# Sinaliza_o_Leds_Buzzer_Conversor_N_vel_L.net
KiCad netlist of a schematic drawn in Altium Designer
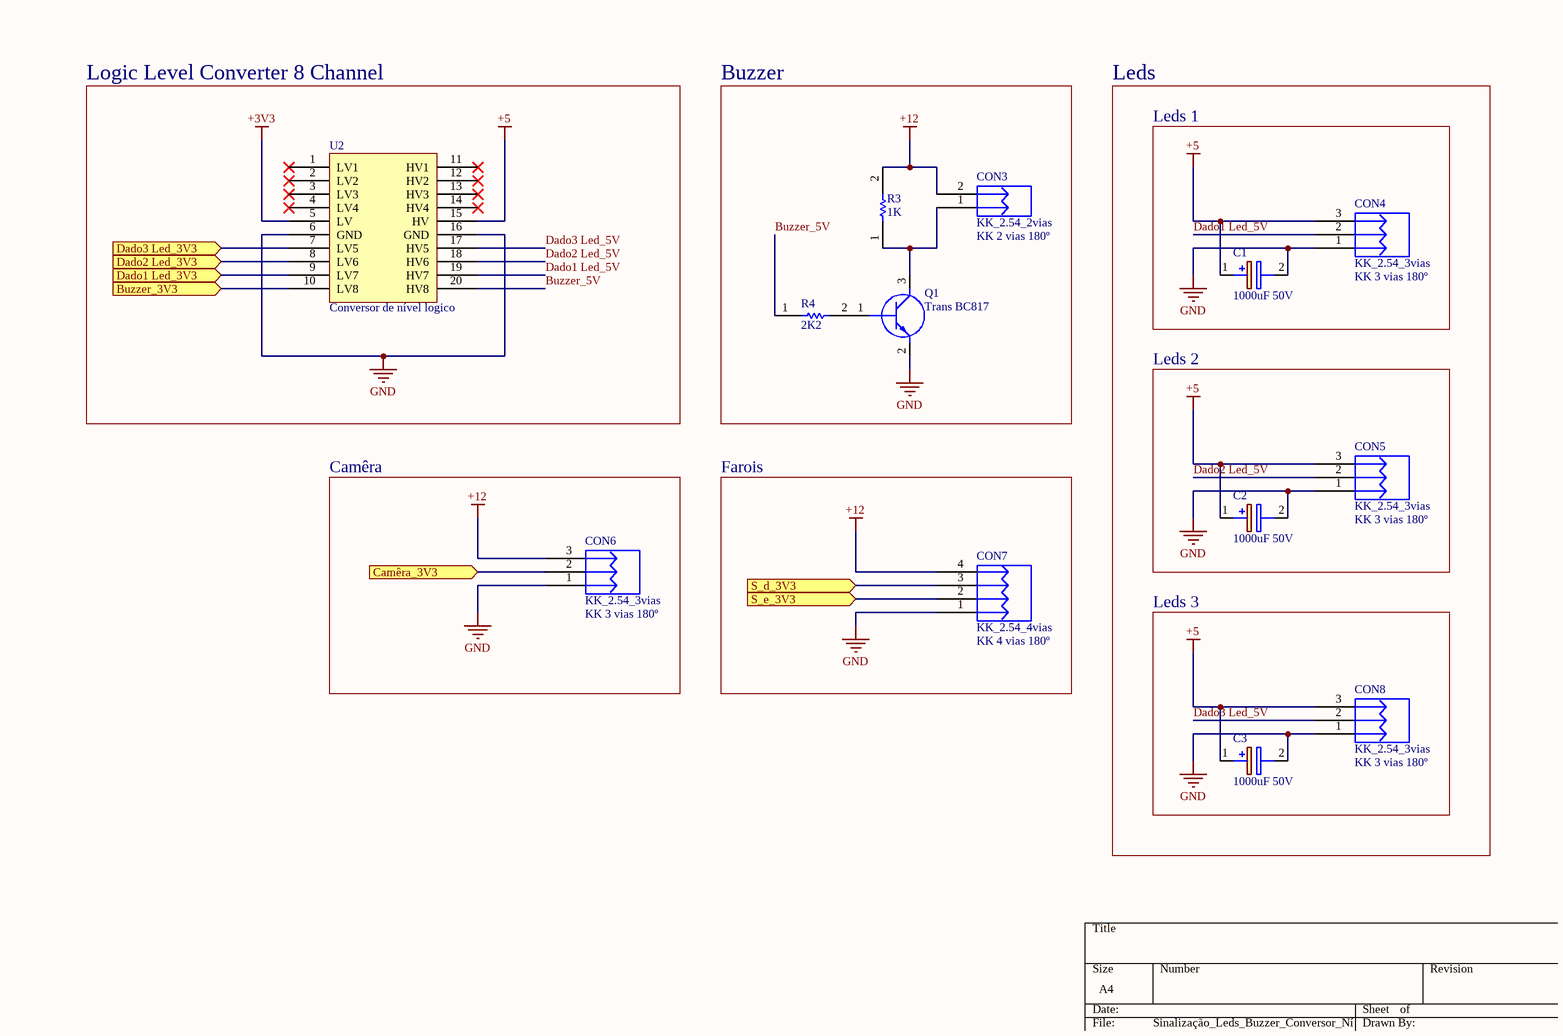
[diagram p0: Sinalização_Leds_Buzzer_Conversor_Nível_Lógico.SchDoc]

(export (version "E")
  (design (tool "Eeschema 10.0.6"))
  (components
    (comp (ref "C1")
      (value "1000uF 50V")
      (footprint "SamacSys:CAPPRD500W62D1300H2650")
      (description "Capacitor Eletrolitico 1000uF 50V")
      (fields
        (field (name "MANUFACTURER_PART_NUMBER") "860010678024")
        (field (name "MOUSER PART NUMBER") "710-860010678024")
      )
      (libsource (lib "Sinalização_Official") (part "1000uF 50V"))
    )
    (comp (ref "C2")
      (value "1000uF 50V")
      (footprint "SamacSys:CAPPRD500W62D1300H2650")
      (description "Capacitor Eletrolitico 1000uF 50V")
      (fields
        (field (name "MANUFACTURER_PART_NUMBER") "860010678024")
        (field (name "MOUSER PART NUMBER") "710-860010678024")
      )
      (libsource (lib "Sinalização_Official") (part "1000uF 50V"))
    )
    (comp (ref "C3")
      (value "1000uF 50V")
      (footprint "SamacSys:CAPPRD500W62D1300H2650")
      (description "Capacitor Eletrolitico 1000uF 50V")
      (fields
        (field (name "MANUFACTURER_PART_NUMBER") "860010678024")
        (field (name "MOUSER PART NUMBER") "710-860010678024")
      )
      (libsource (lib "Sinalização_Official") (part "1000uF 50V"))
    )
    (comp (ref "CON3")
      (value "KK_2.54_2vias")
      (footprint "KK_2VIAS_180º")
      (description "Conector KK 2.54mm 2 vias")
      (fields (field (name "VALOR") "KK 2 vias 180º"))
      (libsource (lib "Sinalização_Official") (part "KK_2.54_2vias"))
    )
    (comp (ref "CON4")
      (value "KK_2.54_3vias")
      (footprint "KK_3vias_180º")
      (description "Conector KK 2.54mm 3 vias")
      (fields (field (name "VALOR") "KK 3 vias 180º"))
      (libsource (lib "Sinalização_Official") (part "KK_2.54_3vias"))
    )
    (comp (ref "CON5")
      (value "KK_2.54_3vias")
      (footprint "KK_3vias_180º")
      (description "Conector KK 2.54mm 3 vias")
      (fields (field (name "VALOR") "KK 3 vias 180º"))
      (libsource (lib "Sinalização_Official") (part "KK_2.54_3vias"))
    )
    (comp (ref "CON6")
      (value "KK_2.54_3vias")
      (footprint "KK_3vias_180º")
      (description "Conector KK 2.54mm 3 vias")
      (fields (field (name "VALOR") "KK 3 vias 180º"))
      (libsource (lib "Sinalização_Official") (part "KK_2.54_3vias"))
    )
    (comp (ref "CON7")
      (value "KK_2.54_4vias")
      (footprint "KK_4vias_180°")
      (description "Conector KK 2.54mm 4 vias")
      (fields (field (name "VALOR") "KK 4 vias 180º"))
      (libsource (lib "Sinalização_Official") (part "KK_2.54_4vias"))
    )
    (comp (ref "CON8")
      (value "KK_2.54_3vias")
      (footprint "KK_3vias_180º")
      (description "Conector KK 2.54mm 3 vias")
      (fields (field (name "VALOR") "KK 3 vias 180º"))
      (libsource (lib "Sinalização_Official") (part "KK_2.54_3vias"))
    )
    (comp (ref "Q1")
      (value "Trans BC817")
      (footprint "SamacSys:SOT96P240X110-3N")
      (description "Transistor BJT NPN BC817-25-7-F")
      (fields
        (field (name "MANUFACTURER_PART_NUMBER") "BC817-25-7-F")
        (field (name "MOUSER PART NUMBER") "621-BC817-25-7-F")
      )
      (libsource (lib "Sinalização_Official") (part "Trans BC817"))
    )
    (comp (ref "R3")
      (value "1K")
      (footprint "SamacSys:RESC3216X60N")
      (description "Resistor")
      (fields
        (field (name "MANUFACTURER_PART_NUMBER") "CRCW12064K70FKEA")
        (field (name "MOUSER PART NUMBER") "71-CRCW1206-4.7K-E3")
      )
      (libsource (lib "Sinalização_Official") (part "Resistor 1206"))
    )
    (comp (ref "R4")
      (value "2K2")
      (footprint "SamacSys:RESC3216X60N")
      (description "Resistor")
      (fields
        (field (name "MANUFACTURER_PART_NUMBER") "CRCW12064K70FKEA")
        (field (name "MOUSER PART NUMBER") "71-CRCW1206-4.7K-E3")
      )
      (libsource (lib "Sinalização_Official") (part "Resistor 1206"))
    )
    (comp (ref "U2")
      (value "Conversor de nível logico")
      (footprint "Conversor de nível lógico")
      (libsource (lib "Sinalização_Official") (part "Conversor de nível logico"))
    )
  )
  (nets
    (net (code "1") (name "+3V3") (class "Default")
      (node (ref "U2") (pin "5") (pinfunction "LV_5") (pintype "passive"))
    )
    (net (code "2") (name "+5") (class "Default")
      (node (ref "C1") (pin "1") (pinfunction "+_1") (pintype "passive"))
      (node (ref "C2") (pin "1") (pinfunction "+_1") (pintype "passive"))
      (node (ref "C3") (pin "1") (pinfunction "+_1") (pintype "passive"))
      (node (ref "CON4") (pin "3") (pintype "passive"))
      (node (ref "CON5") (pin "3") (pintype "passive"))
      (node (ref "CON8") (pin "3") (pintype "passive"))
      (node (ref "U2") (pin "15") (pinfunction "HV_15") (pintype "passive"))
    )
    (net (code "3") (name "+12") (class "Default")
      (node (ref "CON3") (pin "2") (pintype "passive"))
      (node (ref "CON6") (pin "3") (pintype "passive"))
      (node (ref "CON7") (pin "4") (pintype "passive"))
      (node (ref "R3") (pin "2") (pinfunction "2_2") (pintype "passive"))
    )
    (net (code "4") (name "/Buzzer_3V3") (class "Default")
      (node (ref "U2") (pin "10") (pinfunction "LV8_10") (pintype "passive"))
    )
    (net (code "5") (name "/Buzzer_5V") (class "Default")
      (node (ref "R4") (pin "1") (pinfunction "1_1") (pintype "passive"))
      (node (ref "U2") (pin "20") (pinfunction "HV8_20") (pintype "passive"))
    )
    (net (code "6") (name "/Camêra_3V3") (class "Default") (node (ref "CON6") (pin "2") (pintype "passive")))
    (net (code "7") (name "/Dado1 Led_3V3") (class "Default")
      (node (ref "U2") (pin "9") (pinfunction "LV7_9") (pintype "passive"))
    )
    (net (code "8") (name "/Dado1 Led_5V") (class "Default")
      (node (ref "CON4") (pin "2") (pintype "passive"))
      (node (ref "U2") (pin "19") (pinfunction "HV7_19") (pintype "passive"))
    )
    (net (code "9") (name "/Dado2 Led_3V3") (class "Default")
      (node (ref "U2") (pin "8") (pinfunction "LV6_8") (pintype "passive"))
    )
    (net (code "10") (name "/Dado2 Led_5V") (class "Default")
      (node (ref "CON5") (pin "2") (pintype "passive"))
      (node (ref "U2") (pin "18") (pinfunction "HV6_18") (pintype "passive"))
    )
    (net (code "11") (name "/Dado3 Led_3V3") (class "Default")
      (node (ref "U2") (pin "7") (pinfunction "LV5_7") (pintype "passive"))
    )
    (net (code "12") (name "/Dado3 Led_5V") (class "Default")
      (node (ref "CON8") (pin "2") (pintype "passive"))
      (node (ref "U2") (pin "17") (pinfunction "HV5_17") (pintype "passive"))
    )
    (net (code "13") (name "/S_d_3V3") (class "Default") (node (ref "CON7") (pin "3") (pintype "passive")))
    (net (code "14") (name "/S_e_3V3") (class "Default") (node (ref "CON7") (pin "2") (pintype "passive")))
    (net (code "15") (name "GND") (class "Default")
      (node (ref "C1") (pin "2") (pinfunction "-_2") (pintype "passive"))
      (node (ref "C2") (pin "2") (pinfunction "-_2") (pintype "passive"))
      (node (ref "C3") (pin "2") (pinfunction "-_2") (pintype "passive"))
      (node (ref "CON4") (pin "1") (pintype "passive"))
      (node (ref "CON5") (pin "1") (pintype "passive"))
      (node (ref "CON6") (pin "1") (pintype "passive"))
      (node (ref "CON7") (pin "1") (pintype "passive"))
      (node (ref "CON8") (pin "1") (pintype "passive"))
      (node (ref "Q1") (pin "2") (pinfunction "E_2") (pintype "passive"))
      (node (ref "U2") (pin "16") (pinfunction "GND_16") (pintype "passive"))
      (node (ref "U2") (pin "6") (pinfunction "GND_6") (pintype "passive"))
    )
    (net (code "16") (name "Net-(Q1-B)") (class "Default")
      (node (ref "Q1") (pin "1") (pinfunction "B_1") (pintype "passive"))
      (node (ref "R4") (pin "2") (pinfunction "2_2") (pintype "passive"))
    )
    (net (code "17") (name "Net-(Q1-C)") (class "Default")
      (node (ref "CON3") (pin "1") (pintype "passive"))
      (node (ref "Q1") (pin "3") (pinfunction "C_3") (pintype "passive"))
      (node (ref "R3") (pin "1") (pinfunction "1_1") (pintype "passive"))
    )
    (net (code "18") (name "unconnected-(U2-HV1-Pad11)") (class "Default")
      (node (ref "U2") (pin "11") (pinfunction "HV1_11") (pintype "passive+no_connect"))
    )
    (net (code "19") (name "unconnected-(U2-HV2-Pad12)") (class "Default")
      (node (ref "U2") (pin "12") (pinfunction "HV2_12") (pintype "passive+no_connect"))
    )
    (net (code "20") (name "unconnected-(U2-HV3-Pad13)") (class "Default")
      (node (ref "U2") (pin "13") (pinfunction "HV3_13") (pintype "passive+no_connect"))
    )
    (net (code "21") (name "unconnected-(U2-HV4-Pad14)") (class "Default")
      (node (ref "U2") (pin "14") (pinfunction "HV4_14") (pintype "passive+no_connect"))
    )
    (net (code "22") (name "unconnected-(U2-LV1-Pad1)") (class "Default")
      (node (ref "U2") (pin "1") (pinfunction "LV1_1") (pintype "passive+no_connect"))
    )
    (net (code "23") (name "unconnected-(U2-LV2-Pad2)") (class "Default")
      (node (ref "U2") (pin "2") (pinfunction "LV2_2") (pintype "passive+no_connect"))
    )
    (net (code "24") (name "unconnected-(U2-LV3-Pad3)") (class "Default")
      (node (ref "U2") (pin "3") (pinfunction "LV3_3") (pintype "passive+no_connect"))
    )
    (net (code "25") (name "unconnected-(U2-LV4-Pad4)") (class "Default")
      (node (ref "U2") (pin "4") (pinfunction "LV4_4") (pintype "passive+no_connect"))
    )
  )
)
